# v1.net
KiCad netlist of a schematic drawn in EAGLE
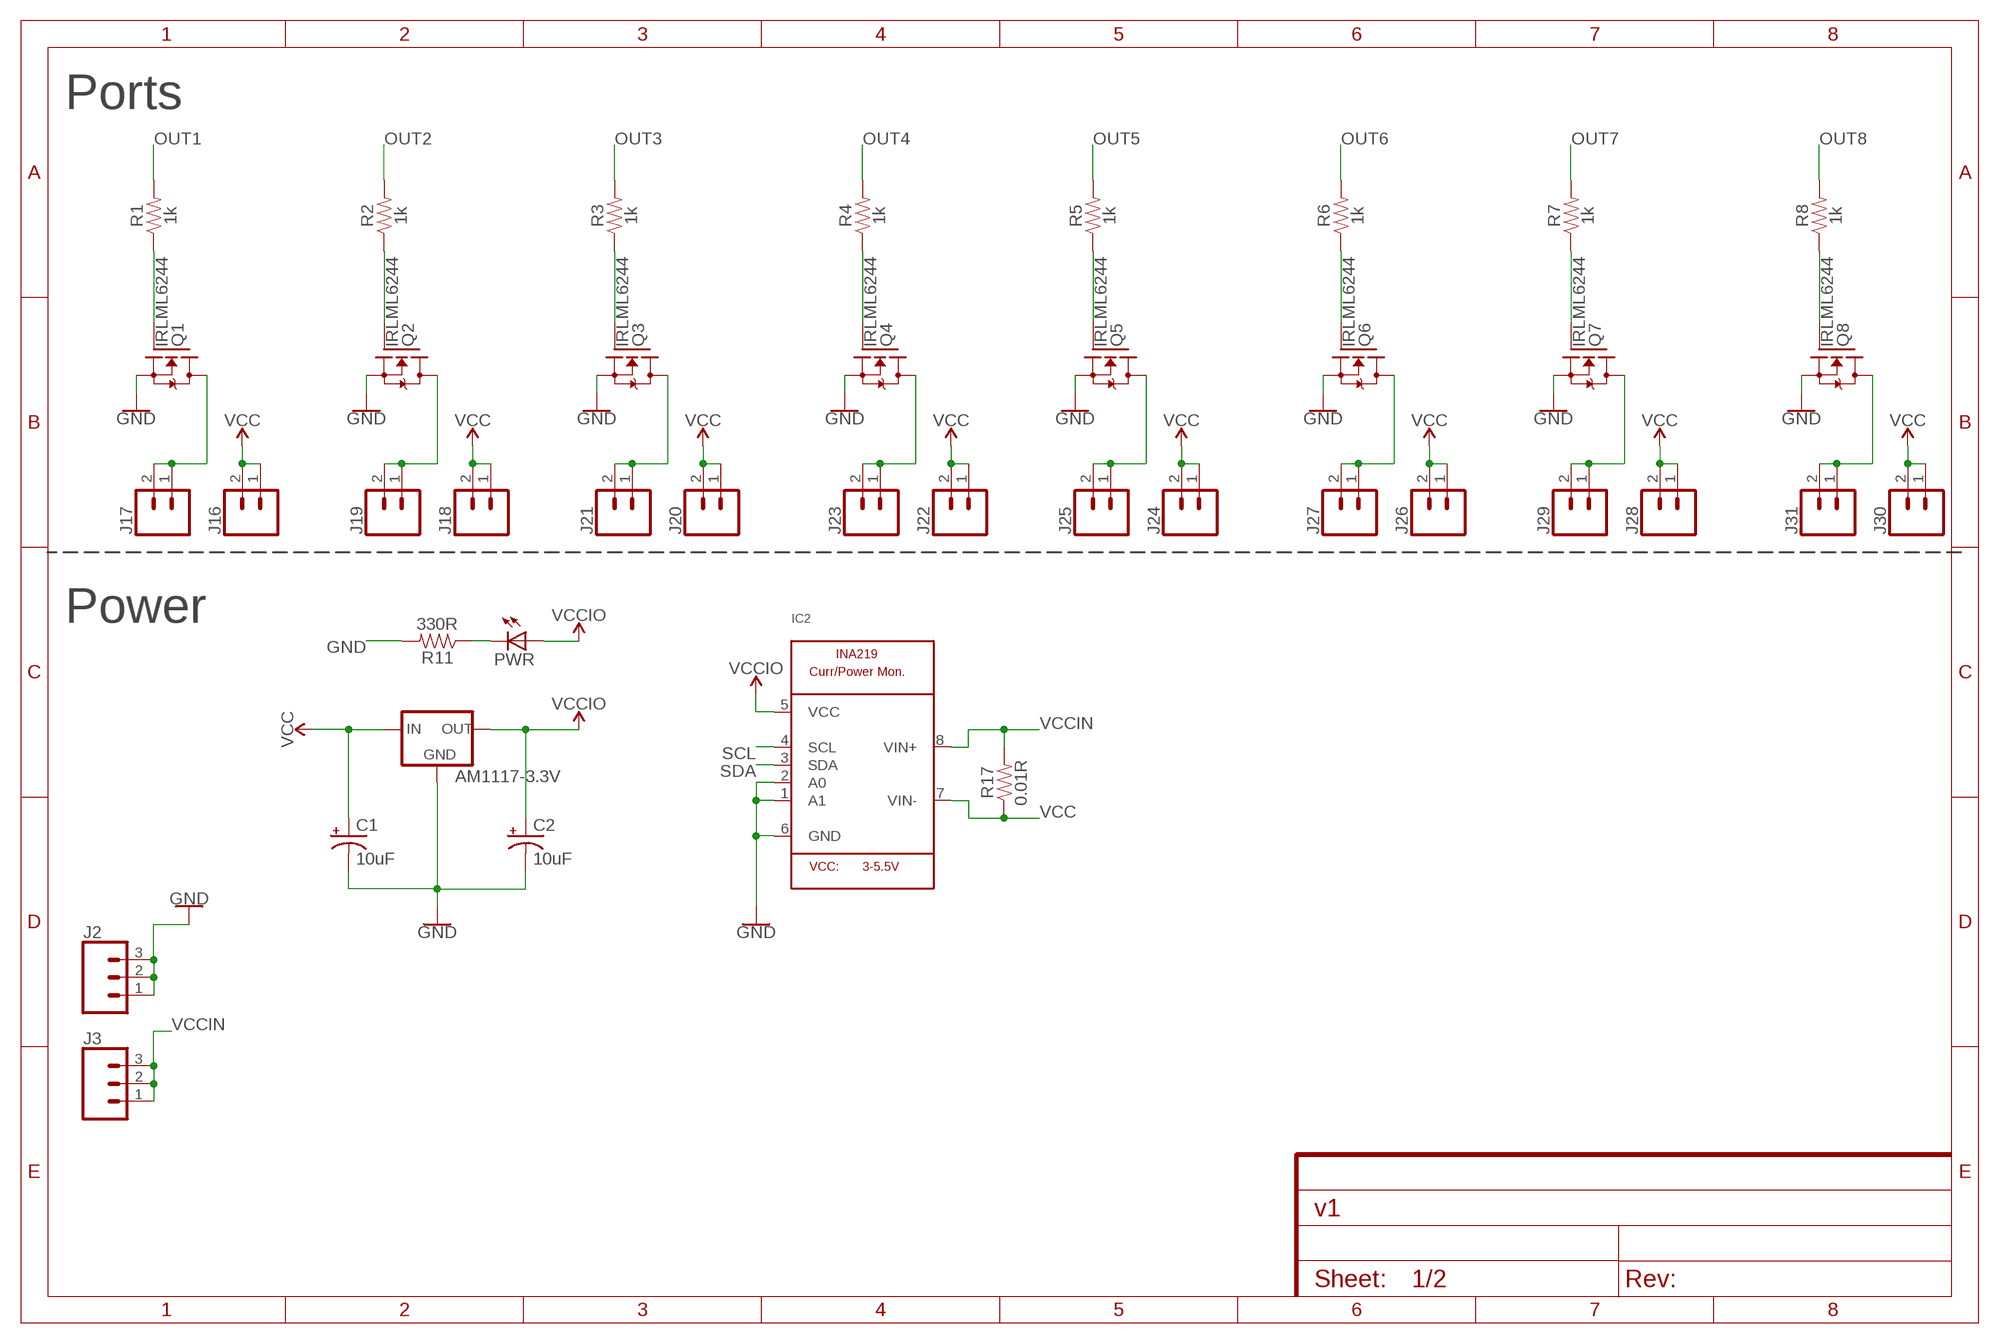
[diagram p0: schematic, sheet 1]
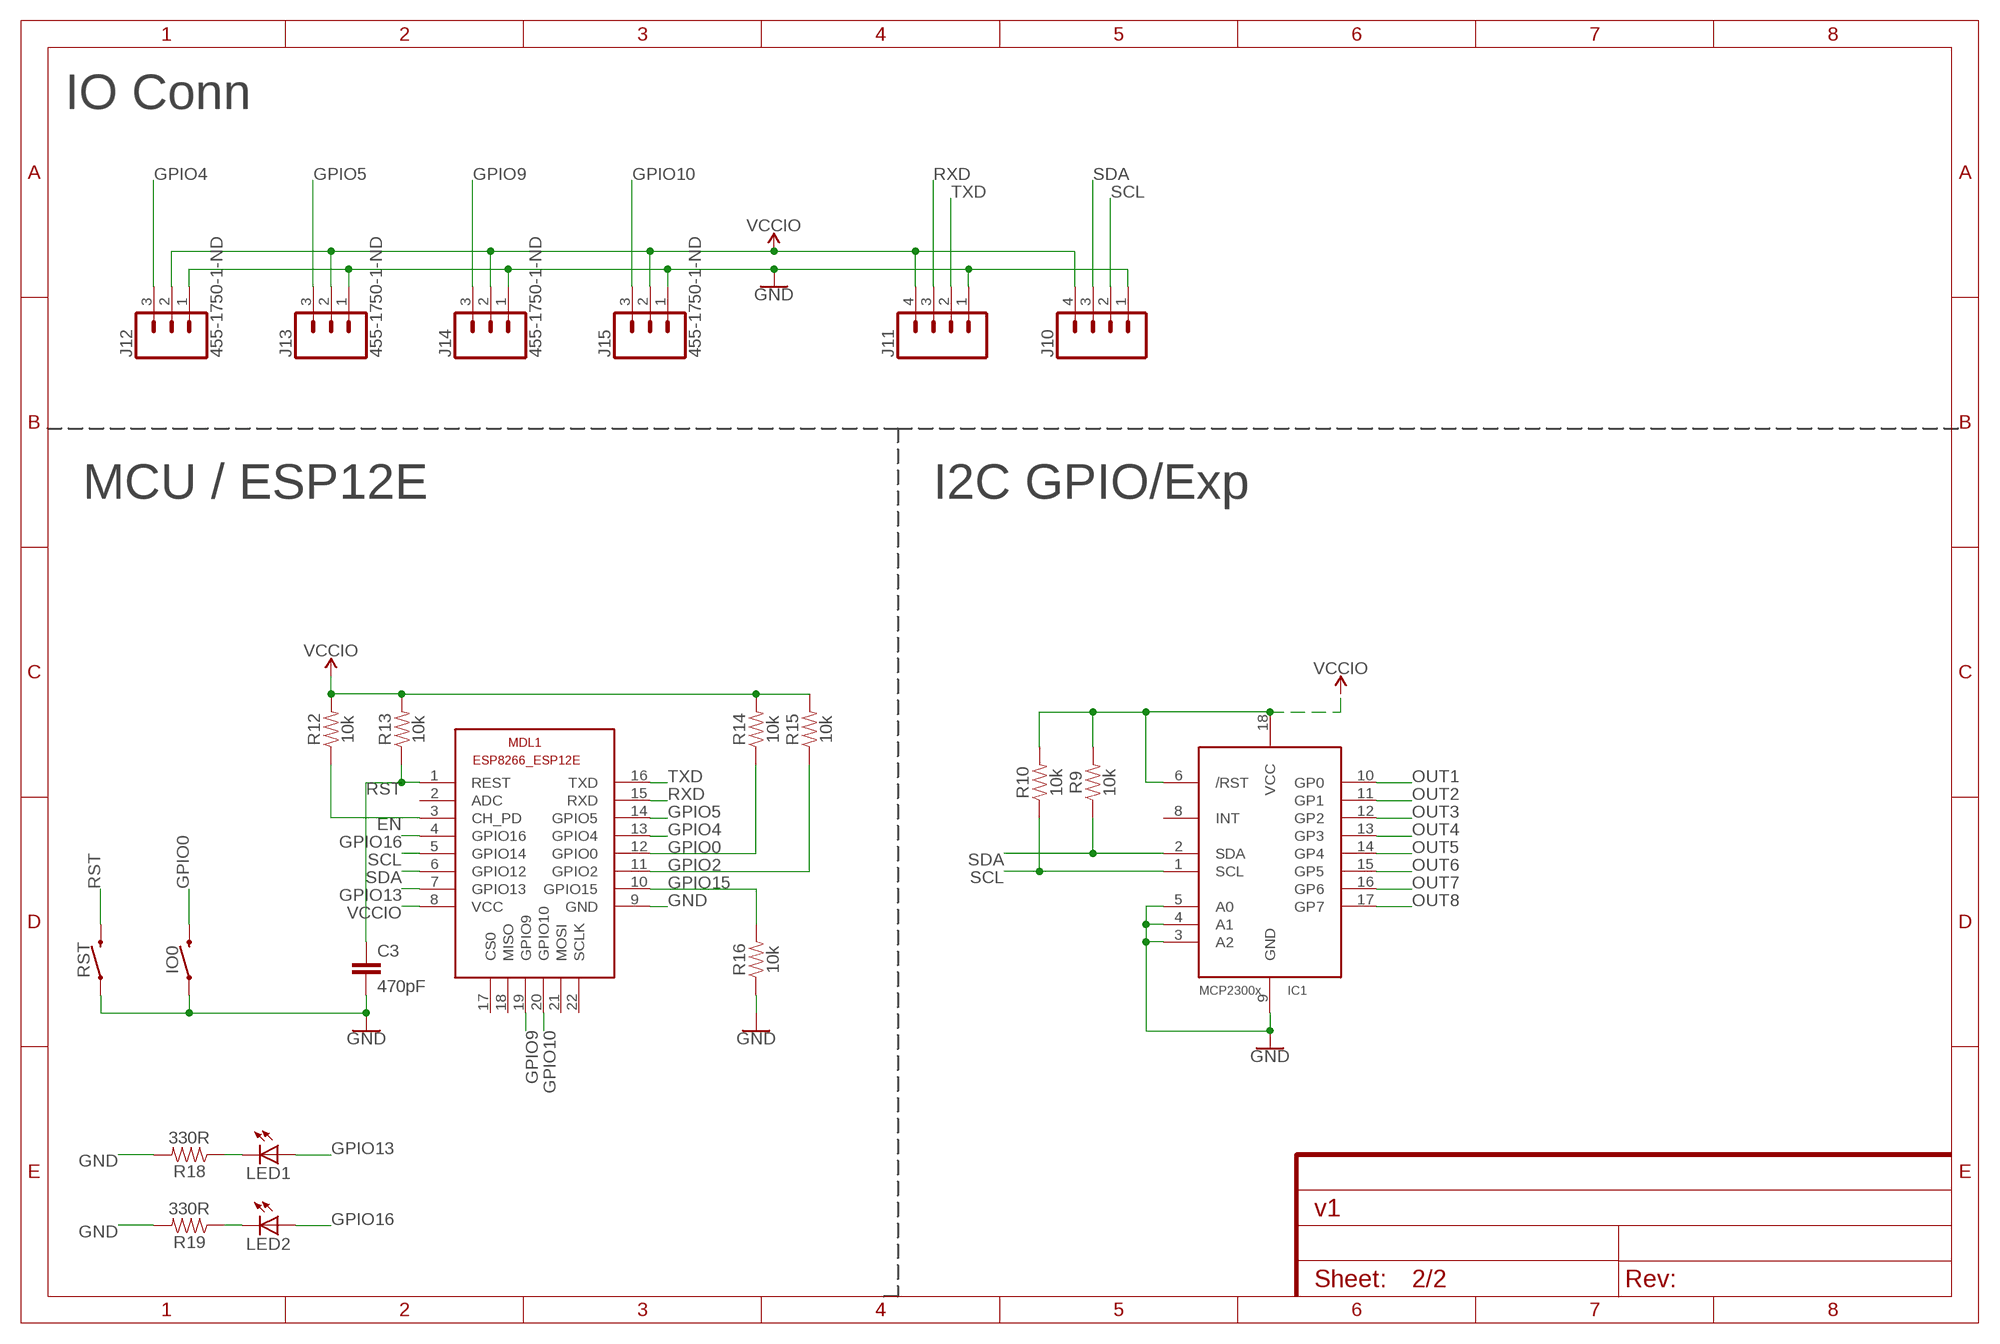
[diagram p1: schematic, sheet 2]

(export (version "E")
  (design (tool "Eeschema 10.0.6"))
  (components
    (comp (ref "AM1117-3.3V")
      (value "V_REG_LD1117VXXLD1117-SMD")
      (footprint "eagle-import:SOT223")
      (libsource (lib "eagle-import") (part "V_REG_LD1117VXXLD1117-SMD"))
    )
    (comp (ref "C1")
      (value "10uF")
      (footprint "eagle-import:EIA3216")
      (libsource (lib "eagle-import") (part "10UF-TANT"))
    )
    (comp (ref "C2")
      (value "10uF")
      (footprint "eagle-import:EIA3216")
      (libsource (lib "eagle-import") (part "10UF-TANT"))
    )
    (comp (ref "IC2")
      (value "INA219SOIC8")
      (footprint "eagle-import:SO08")
      (libsource (lib "eagle-import") (part "INA219SOIC8"))
    )
    (comp (ref "J2")
      (value "CONN_03LONGPADS")
      (footprint "eagle-import:1X03_LONGPADS")
      (libsource (lib "eagle-import") (part "CONN_03LONGPADS"))
    )
    (comp (ref "J3")
      (value "CONN_03LONGPADS")
      (footprint "eagle-import:1X03_LONGPADS")
      (libsource (lib "eagle-import") (part "CONN_03LONGPADS"))
    )
    (comp (ref "J16")
      (value "CONN_02")
      (footprint "eagle-import:1X02")
      (libsource (lib "eagle-import") (part "CONN_02"))
    )
    (comp (ref "J17")
      (value "CONN_02")
      (footprint "eagle-import:1X02")
      (libsource (lib "eagle-import") (part "CONN_02"))
    )
    (comp (ref "J18")
      (value "CONN_02")
      (footprint "eagle-import:1X02")
      (libsource (lib "eagle-import") (part "CONN_02"))
    )
    (comp (ref "J19")
      (value "CONN_02")
      (footprint "eagle-import:1X02")
      (libsource (lib "eagle-import") (part "CONN_02"))
    )
    (comp (ref "J20")
      (value "CONN_02")
      (footprint "eagle-import:1X02")
      (libsource (lib "eagle-import") (part "CONN_02"))
    )
    (comp (ref "J21")
      (value "CONN_02")
      (footprint "eagle-import:1X02")
      (libsource (lib "eagle-import") (part "CONN_02"))
    )
    (comp (ref "J22")
      (value "CONN_02")
      (footprint "eagle-import:1X02")
      (libsource (lib "eagle-import") (part "CONN_02"))
    )
    (comp (ref "J23")
      (value "CONN_02")
      (footprint "eagle-import:1X02")
      (libsource (lib "eagle-import") (part "CONN_02"))
    )
    (comp (ref "J24")
      (value "CONN_02")
      (footprint "eagle-import:1X02")
      (libsource (lib "eagle-import") (part "CONN_02"))
    )
    (comp (ref "J25")
      (value "CONN_02")
      (footprint "eagle-import:1X02")
      (libsource (lib "eagle-import") (part "CONN_02"))
    )
    (comp (ref "J26")
      (value "CONN_02")
      (footprint "eagle-import:1X02")
      (libsource (lib "eagle-import") (part "CONN_02"))
    )
    (comp (ref "J27")
      (value "CONN_02")
      (footprint "eagle-import:1X02")
      (libsource (lib "eagle-import") (part "CONN_02"))
    )
    (comp (ref "J28")
      (value "CONN_02")
      (footprint "eagle-import:1X02")
      (libsource (lib "eagle-import") (part "CONN_02"))
    )
    (comp (ref "J29")
      (value "CONN_02")
      (footprint "eagle-import:1X02")
      (libsource (lib "eagle-import") (part "CONN_02"))
    )
    (comp (ref "J30")
      (value "CONN_02")
      (footprint "eagle-import:1X02")
      (libsource (lib "eagle-import") (part "CONN_02"))
    )
    (comp (ref "J31")
      (value "CONN_02")
      (footprint "eagle-import:1X02")
      (libsource (lib "eagle-import") (part "CONN_02"))
    )
    (comp (ref "PWR")
      (value "LEDCHIP-LED0805")
      (footprint "eagle-import:CHIP-LED0805")
      (libsource (lib "eagle-import") (part "LEDCHIP-LED0805"))
    )
    (comp (ref "Q1")
      (value "IRLML6244")
      (footprint "eagle-import:SOT23")
      (fields
        (field (name "MF") "Internat. Rectifier")
        (field (name "MPN") "IRLML6244TRPbF")
        (field (name "SPICEPREFIX") "Q")
      )
      (libsource (lib "eagle-import") (part "IRLML6244"))
    )
    (comp (ref "Q2")
      (value "IRLML6244")
      (footprint "eagle-import:SOT23")
      (fields (field (name "MF") "Internat. Rectifier") (field (name "MPN") "IRLML6244TRPbF"))
      (libsource (lib "eagle-import") (part "IRLML6244"))
    )
    (comp (ref "Q3")
      (value "IRLML6244")
      (footprint "eagle-import:SOT23")
      (fields (field (name "MF") "Internat. Rectifier") (field (name "MPN") "IRLML6244TRPbF"))
      (libsource (lib "eagle-import") (part "IRLML6244"))
    )
    (comp (ref "Q4")
      (value "IRLML6244")
      (footprint "eagle-import:SOT23")
      (fields (field (name "MF") "Internat. Rectifier") (field (name "MPN") "IRLML6244TRPbF"))
      (libsource (lib "eagle-import") (part "IRLML6244"))
    )
    (comp (ref "Q5")
      (value "IRLML6244")
      (footprint "eagle-import:SOT23")
      (fields (field (name "MF") "Internat. Rectifier") (field (name "MPN") "IRLML6244TRPbF"))
      (libsource (lib "eagle-import") (part "IRLML6244"))
    )
    (comp (ref "Q6")
      (value "IRLML6244")
      (footprint "eagle-import:SOT23")
      (fields (field (name "MF") "Internat. Rectifier") (field (name "MPN") "IRLML6244TRPbF"))
      (libsource (lib "eagle-import") (part "IRLML6244"))
    )
    (comp (ref "Q7")
      (value "IRLML6244")
      (footprint "eagle-import:SOT23")
      (fields (field (name "MF") "Internat. Rectifier") (field (name "MPN") "IRLML6244TRPbF"))
      (libsource (lib "eagle-import") (part "IRLML6244"))
    )
    (comp (ref "Q8")
      (value "IRLML6244")
      (footprint "eagle-import:SOT23")
      (fields (field (name "MF") "Internat. Rectifier") (field (name "MPN") "IRLML6244TRPbF"))
      (libsource (lib "eagle-import") (part "IRLML6244"))
    )
    (comp (ref "R1")
      (value "1k")
      (footprint "eagle-import:0805")
      (fields (field (name "SPICEPREFIX") "R"))
      (libsource (lib "eagle-import") (part "RESISTOR0805"))
    )
    (comp (ref "R2")
      (value "1k")
      (footprint "eagle-import:0805")
      (libsource (lib "eagle-import") (part "RESISTOR0805"))
    )
    (comp (ref "R3")
      (value "1k")
      (footprint "eagle-import:0805")
      (libsource (lib "eagle-import") (part "RESISTOR0805"))
    )
    (comp (ref "R4")
      (value "1k")
      (footprint "eagle-import:0805")
      (libsource (lib "eagle-import") (part "RESISTOR0805"))
    )
    (comp (ref "R5")
      (value "1k")
      (footprint "eagle-import:0805")
      (libsource (lib "eagle-import") (part "RESISTOR0805"))
    )
    (comp (ref "R6")
      (value "1k")
      (footprint "eagle-import:0805")
      (libsource (lib "eagle-import") (part "RESISTOR0805"))
    )
    (comp (ref "R7")
      (value "1k")
      (footprint "eagle-import:0805")
      (libsource (lib "eagle-import") (part "RESISTOR0805"))
    )
    (comp (ref "R8")
      (value "1k")
      (footprint "eagle-import:0805")
      (libsource (lib "eagle-import") (part "RESISTOR0805"))
    )
    (comp (ref "R11")
      (value "330R")
      (footprint "eagle-import:0805")
      (libsource (lib "eagle-import") (part "RESISTOR0805"))
    )
    (comp (ref "R17")
      (value "0.01R")
      (footprint "eagle-import:2512")
      (libsource (lib "eagle-import") (part "0.05OHM-2512-3W-1%"))
    )
    (comp (ref "C3")
      (value "470pF")
      (footprint "eagle-import:0805")
      (libsource (lib "eagle-import") (part "1.0UF-0805-25V-(+80/-20%)"))
    )
    (comp (ref "IC1")
      (value "MCP23008/SO")
      (footprint "eagle-import:SO18W")
      (libsource (lib "eagle-import") (part "MCP23008/SO"))
    )
    (comp (ref "IO0")
      (value "MOMENTARY-SWITCH-SPST-SMD-6.0X3.5MM")
      (footprint "eagle-import:TACTILE_SWITCH_SMD_6.0X3.5MM")
      (libsource (lib "eagle-import") (part "MOMENTARY-SWITCH-SPST-SMD-6.0X3.5MM"))
    )
    (comp (ref "J10")
      (value "CONN_04PTH")
      (footprint "eagle-import:1X04")
      (libsource (lib "eagle-import") (part "CONN_04PTH"))
    )
    (comp (ref "J11")
      (value "CONN_04PTH")
      (footprint "eagle-import:1X04")
      (libsource (lib "eagle-import") (part "CONN_04PTH"))
    )
    (comp (ref "J12")
      (value "455-1750-1-ND")
      (footprint "eagle-import:1X03")
      (libsource (lib "eagle-import") (part "CONN_03"))
    )
    (comp (ref "J13")
      (value "455-1750-1-ND")
      (footprint "eagle-import:1X03")
      (libsource (lib "eagle-import") (part "CONN_03"))
    )
    (comp (ref "J14")
      (value "455-1750-1-ND")
      (footprint "eagle-import:1X03")
      (libsource (lib "eagle-import") (part "CONN_03"))
    )
    (comp (ref "J15")
      (value "455-1750-1-ND")
      (footprint "eagle-import:1X03")
      (libsource (lib "eagle-import") (part "CONN_03"))
    )
    (comp (ref "LED1")
      (value "LEDCHIP-LED0805")
      (footprint "eagle-import:CHIP-LED0805")
      (libsource (lib "eagle-import") (part "LEDCHIP-LED0805"))
    )
    (comp (ref "LED2")
      (value "LEDCHIP-LED0805")
      (footprint "eagle-import:CHIP-LED0805")
      (libsource (lib "eagle-import") (part "LEDCHIP-LED0805"))
    )
    (comp (ref "MDL1")
      (value "ESP8266-12EESP8266-ESP12E")
      (footprint "eagle-import:ESP8266-ESP12E")
      (libsource (lib "eagle-import") (part "ESP8266-12EESP8266-ESP12E"))
    )
    (comp (ref "R9")
      (value "10k")
      (footprint "eagle-import:0805")
      (libsource (lib "eagle-import") (part "RESISTOR0805"))
    )
    (comp (ref "R10")
      (value "10k")
      (footprint "eagle-import:0805")
      (libsource (lib "eagle-import") (part "RESISTOR0805"))
    )
    (comp (ref "R12")
      (value "10k")
      (footprint "eagle-import:0805")
      (libsource (lib "eagle-import") (part "RESISTOR0805"))
    )
    (comp (ref "R13")
      (value "10k")
      (footprint "eagle-import:0805")
      (libsource (lib "eagle-import") (part "RESISTOR0805"))
    )
    (comp (ref "R14")
      (value "10k")
      (footprint "eagle-import:0805")
      (libsource (lib "eagle-import") (part "RESISTOR0805"))
    )
    (comp (ref "R15")
      (value "10k")
      (footprint "eagle-import:0805")
      (libsource (lib "eagle-import") (part "RESISTOR0805"))
    )
    (comp (ref "R16")
      (value "10k")
      (footprint "eagle-import:0805")
      (libsource (lib "eagle-import") (part "RESISTOR0805"))
    )
    (comp (ref "R18")
      (value "330R")
      (footprint "eagle-import:0805")
      (libsource (lib "eagle-import") (part "RESISTOR0805"))
    )
    (comp (ref "R19")
      (value "330R")
      (footprint "eagle-import:0805")
      (libsource (lib "eagle-import") (part "RESISTOR0805"))
    )
    (comp (ref "RST")
      (value "MOMENTARY-SWITCH-SPST-SMD-6.0X3.5MM")
      (footprint "eagle-import:TACTILE_SWITCH_SMD_6.0X3.5MM")
      (libsource (lib "eagle-import") (part "MOMENTARY-SWITCH-SPST-SMD-6.0X3.5MM"))
    )
  )
  (nets
    (net (code "1") (name "EN") (class "Default")
      (node (ref "MDL1") (pin "3") (pinfunction "CH_PD_3") (pintype "bidirectional"))
      (node (ref "R12") (pin "1") (pinfunction "1_1") (pintype "passive"))
    )
    (net (code "2") (name "GND") (class "Default")
      (node (ref "AM1117-3.3V") (pin "1") (pinfunction "GND_1") (pintype "input"))
      (node (ref "C1") (pin "C") (pinfunction "-_C") (pintype "passive"))
      (node (ref "C2") (pin "C") (pinfunction "-_C") (pintype "passive"))
      (node (ref "C3") (pin "2") (pinfunction "2_2") (pintype "passive"))
      (node (ref "IC1") (pin "3") (pinfunction "A2_3") (pintype "input"))
      (node (ref "IC1") (pin "4") (pinfunction "A1_4") (pintype "input"))
      (node (ref "IC1") (pin "5") (pinfunction "A0_5") (pintype "input"))
      (node (ref "IC1") (pin "9") (pinfunction "GND_9") (pintype "power_in"))
      (node (ref "IC2") (pin "1") (pinfunction "A1_1") (pintype "bidirectional"))
      (node (ref "IC2") (pin "2") (pinfunction "A0_2") (pintype "bidirectional"))
      (node (ref "IC2") (pin "6") (pinfunction "GND_6") (pintype "bidirectional"))
      (node (ref "IO0") (pin "1") (pinfunction "1_1") (pintype "passive"))
      (node (ref "J10") (pin "1") (pinfunction "1_1") (pintype "passive"))
      (node (ref "J11") (pin "1") (pinfunction "1_1") (pintype "passive"))
      (node (ref "J12") (pin "1") (pinfunction "1_1") (pintype "passive"))
      (node (ref "J13") (pin "1") (pinfunction "1_1") (pintype "passive"))
      (node (ref "J14") (pin "1") (pinfunction "1_1") (pintype "passive"))
      (node (ref "J15") (pin "1") (pinfunction "1_1") (pintype "passive"))
      (node (ref "J2") (pin "1") (pinfunction "1_1") (pintype "passive"))
      (node (ref "J2") (pin "2") (pinfunction "2_2") (pintype "passive"))
      (node (ref "J2") (pin "3") (pinfunction "3_3") (pintype "passive"))
      (node (ref "MDL1") (pin "9") (pinfunction "GND_9") (pintype "bidirectional"))
      (node (ref "Q1") (pin "2") (pinfunction "S_2") (pintype "passive"))
      (node (ref "Q2") (pin "2") (pinfunction "S_2") (pintype "passive"))
      (node (ref "Q3") (pin "2") (pinfunction "S_2") (pintype "passive"))
      (node (ref "Q4") (pin "2") (pinfunction "S_2") (pintype "passive"))
      (node (ref "Q5") (pin "2") (pinfunction "S_2") (pintype "passive"))
      (node (ref "Q6") (pin "2") (pinfunction "S_2") (pintype "passive"))
      (node (ref "Q7") (pin "2") (pinfunction "S_2") (pintype "passive"))
      (node (ref "Q8") (pin "2") (pinfunction "S_2") (pintype "passive"))
      (node (ref "R11") (pin "2") (pinfunction "2_2") (pintype "passive"))
      (node (ref "R16") (pin "1") (pinfunction "1_1") (pintype "passive"))
      (node (ref "R18") (pin "2") (pinfunction "2_2") (pintype "passive"))
      (node (ref "R19") (pin "2") (pinfunction "2_2") (pintype "passive"))
      (node (ref "RST") (pin "1") (pinfunction "1_1") (pintype "passive"))
    )
    (net (code "3") (name "GPIO0") (class "Default")
      (node (ref "IO0") (pin "2") (pinfunction "2_2") (pintype "passive"))
      (node (ref "MDL1") (pin "12") (pinfunction "GPIO0_12") (pintype "bidirectional"))
      (node (ref "R14") (pin "1") (pinfunction "1_1") (pintype "passive"))
    )
    (net (code "4") (name "GPIO2") (class "Default")
      (node (ref "MDL1") (pin "11") (pinfunction "GPIO2_11") (pintype "bidirectional"))
      (node (ref "R15") (pin "1") (pinfunction "1_1") (pintype "passive"))
    )
    (net (code "5") (name "GPIO4") (class "Default")
      (node (ref "J12") (pin "3") (pinfunction "3_3") (pintype "passive"))
      (node (ref "MDL1") (pin "13") (pinfunction "GPIO4_13") (pintype "bidirectional"))
    )
    (net (code "6") (name "GPIO5") (class "Default")
      (node (ref "J13") (pin "3") (pinfunction "3_3") (pintype "passive"))
      (node (ref "MDL1") (pin "14") (pinfunction "GPIO5_14") (pintype "bidirectional"))
    )
    (net (code "7") (name "GPIO9") (class "Default")
      (node (ref "J14") (pin "3") (pinfunction "3_3") (pintype "passive"))
      (node (ref "MDL1") (pin "19") (pinfunction "GPIO9_19") (pintype "bidirectional"))
    )
    (net (code "8") (name "GPIO10") (class "Default")
      (node (ref "J15") (pin "3") (pinfunction "3_3") (pintype "passive"))
      (node (ref "MDL1") (pin "20") (pinfunction "GPIO10_20") (pintype "bidirectional"))
    )
    (net (code "9") (name "GPIO13") (class "Default")
      (node (ref "LED1") (pin "A") (pinfunction "A_A") (pintype "passive"))
      (node (ref "MDL1") (pin "7") (pinfunction "GPIO13_7") (pintype "bidirectional"))
    )
    (net (code "10") (name "GPIO15") (class "Default")
      (node (ref "MDL1") (pin "10") (pinfunction "GPIO15_10") (pintype "bidirectional"))
      (node (ref "R16") (pin "2") (pinfunction "2_2") (pintype "passive"))
    )
    (net (code "11") (name "GPIO16") (class "Default")
      (node (ref "LED2") (pin "A") (pinfunction "A_A") (pintype "passive"))
      (node (ref "MDL1") (pin "4") (pinfunction "GPIO16_4") (pintype "bidirectional"))
    )
    (net (code "12") (name "Net-(LED1-PadC)") (class "Default")
      (node (ref "LED1") (pin "C") (pinfunction "C_C") (pintype "passive"))
      (node (ref "R18") (pin "1") (pinfunction "1_1") (pintype "passive"))
    )
    (net (code "13") (name "Net-(LED2-PadC)") (class "Default")
      (node (ref "LED2") (pin "C") (pinfunction "C_C") (pintype "passive"))
      (node (ref "R19") (pin "1") (pinfunction "1_1") (pintype "passive"))
    )
    (net (code "14") (name "Net-(PWR-PadC)") (class "Default")
      (node (ref "PWR") (pin "C") (pinfunction "C_C") (pintype "passive"))
      (node (ref "R11") (pin "1") (pinfunction "1_1") (pintype "passive"))
    )
    (net (code "15") (name "Net-(Q1-D)") (class "Default")
      (node (ref "J17") (pin "1") (pinfunction "1_1") (pintype "passive"))
      (node (ref "J17") (pin "2") (pinfunction "2_2") (pintype "passive"))
      (node (ref "Q1") (pin "3") (pinfunction "D_3") (pintype "passive"))
    )
    (net (code "16") (name "Net-(Q1-G)") (class "Default")
      (node (ref "Q1") (pin "1") (pinfunction "G_1") (pintype "passive"))
      (node (ref "R1") (pin "1") (pinfunction "1_1") (pintype "passive"))
    )
    (net (code "17") (name "Net-(Q2-D)") (class "Default")
      (node (ref "J19") (pin "1") (pinfunction "1_1") (pintype "passive"))
      (node (ref "J19") (pin "2") (pinfunction "2_2") (pintype "passive"))
      (node (ref "Q2") (pin "3") (pinfunction "D_3") (pintype "passive"))
    )
    (net (code "18") (name "Net-(Q2-G)") (class "Default")
      (node (ref "Q2") (pin "1") (pinfunction "G_1") (pintype "passive"))
      (node (ref "R2") (pin "1") (pinfunction "1_1") (pintype "passive"))
    )
    (net (code "19") (name "Net-(Q3-D)") (class "Default")
      (node (ref "J21") (pin "1") (pinfunction "1_1") (pintype "passive"))
      (node (ref "J21") (pin "2") (pinfunction "2_2") (pintype "passive"))
      (node (ref "Q3") (pin "3") (pinfunction "D_3") (pintype "passive"))
    )
    (net (code "20") (name "Net-(Q3-G)") (class "Default")
      (node (ref "Q3") (pin "1") (pinfunction "G_1") (pintype "passive"))
      (node (ref "R3") (pin "1") (pinfunction "1_1") (pintype "passive"))
    )
    (net (code "21") (name "Net-(Q4-D)") (class "Default")
      (node (ref "J23") (pin "1") (pinfunction "1_1") (pintype "passive"))
      (node (ref "J23") (pin "2") (pinfunction "2_2") (pintype "passive"))
      (node (ref "Q4") (pin "3") (pinfunction "D_3") (pintype "passive"))
    )
    (net (code "22") (name "Net-(Q4-G)") (class "Default")
      (node (ref "Q4") (pin "1") (pinfunction "G_1") (pintype "passive"))
      (node (ref "R4") (pin "1") (pinfunction "1_1") (pintype "passive"))
    )
    (net (code "23") (name "Net-(Q5-D)") (class "Default")
      (node (ref "J25") (pin "1") (pinfunction "1_1") (pintype "passive"))
      (node (ref "J25") (pin "2") (pinfunction "2_2") (pintype "passive"))
      (node (ref "Q5") (pin "3") (pinfunction "D_3") (pintype "passive"))
    )
    (net (code "24") (name "Net-(Q5-G)") (class "Default")
      (node (ref "Q5") (pin "1") (pinfunction "G_1") (pintype "passive"))
      (node (ref "R5") (pin "1") (pinfunction "1_1") (pintype "passive"))
    )
    (net (code "25") (name "Net-(Q6-D)") (class "Default")
      (node (ref "J27") (pin "1") (pinfunction "1_1") (pintype "passive"))
      (node (ref "J27") (pin "2") (pinfunction "2_2") (pintype "passive"))
      (node (ref "Q6") (pin "3") (pinfunction "D_3") (pintype "passive"))
    )
    (net (code "26") (name "Net-(Q6-G)") (class "Default")
      (node (ref "Q6") (pin "1") (pinfunction "G_1") (pintype "passive"))
      (node (ref "R6") (pin "1") (pinfunction "1_1") (pintype "passive"))
    )
    (net (code "27") (name "Net-(Q7-D)") (class "Default")
      (node (ref "J29") (pin "1") (pinfunction "1_1") (pintype "passive"))
      (node (ref "J29") (pin "2") (pinfunction "2_2") (pintype "passive"))
      (node (ref "Q7") (pin "3") (pinfunction "D_3") (pintype "passive"))
    )
    (net (code "28") (name "Net-(Q7-G)") (class "Default")
      (node (ref "Q7") (pin "1") (pinfunction "G_1") (pintype "passive"))
      (node (ref "R7") (pin "1") (pinfunction "1_1") (pintype "passive"))
    )
    (net (code "29") (name "Net-(Q8-D)") (class "Default")
      (node (ref "J31") (pin "1") (pinfunction "1_1") (pintype "passive"))
      (node (ref "J31") (pin "2") (pinfunction "2_2") (pintype "passive"))
      (node (ref "Q8") (pin "3") (pinfunction "D_3") (pintype "passive"))
    )
    (net (code "30") (name "Net-(Q8-G)") (class "Default")
      (node (ref "Q8") (pin "1") (pinfunction "G_1") (pintype "passive"))
      (node (ref "R8") (pin "1") (pinfunction "1_1") (pintype "passive"))
    )
    (net (code "31") (name "OUT1") (class "Default")
      (node (ref "IC1") (pin "10") (pinfunction "GP0_10") (pintype "bidirectional"))
      (node (ref "R1") (pin "2") (pinfunction "2_2") (pintype "passive"))
    )
    (net (code "32") (name "OUT2") (class "Default")
      (node (ref "IC1") (pin "11") (pinfunction "GP1_11") (pintype "bidirectional"))
      (node (ref "R2") (pin "2") (pinfunction "2_2") (pintype "passive"))
    )
    (net (code "33") (name "OUT3") (class "Default")
      (node (ref "IC1") (pin "12") (pinfunction "GP2_12") (pintype "bidirectional"))
      (node (ref "R3") (pin "2") (pinfunction "2_2") (pintype "passive"))
    )
    (net (code "34") (name "OUT4") (class "Default")
      (node (ref "IC1") (pin "13") (pinfunction "GP3_13") (pintype "bidirectional"))
      (node (ref "R4") (pin "2") (pinfunction "2_2") (pintype "passive"))
    )
    (net (code "35") (name "OUT5") (class "Default")
      (node (ref "IC1") (pin "14") (pinfunction "GP4_14") (pintype "bidirectional"))
      (node (ref "R5") (pin "2") (pinfunction "2_2") (pintype "passive"))
    )
    (net (code "36") (name "OUT6") (class "Default")
      (node (ref "IC1") (pin "15") (pinfunction "GP5_15") (pintype "bidirectional"))
      (node (ref "R6") (pin "2") (pinfunction "2_2") (pintype "passive"))
    )
    (net (code "37") (name "OUT7") (class "Default")
      (node (ref "IC1") (pin "16") (pinfunction "GP6_16") (pintype "bidirectional"))
      (node (ref "R7") (pin "2") (pinfunction "2_2") (pintype "passive"))
    )
    (net (code "38") (name "OUT8") (class "Default")
      (node (ref "IC1") (pin "17") (pinfunction "GP7_17") (pintype "bidirectional"))
      (node (ref "R8") (pin "2") (pinfunction "2_2") (pintype "passive"))
    )
    (net (code "39") (name "RST") (class "Default")
      (node (ref "C3") (pin "1") (pinfunction "1_1") (pintype "passive"))
      (node (ref "MDL1") (pin "1") (pinfunction "REST_1") (pintype "bidirectional"))
      (node (ref "R13") (pin "1") (pinfunction "1_1") (pintype "passive"))
      (node (ref "RST") (pin "2") (pinfunction "2_2") (pintype "passive"))
    )
    (net (code "40") (name "RXD") (class "Default")
      (node (ref "J11") (pin "3") (pinfunction "3_3") (pintype "passive"))
      (node (ref "MDL1") (pin "15") (pinfunction "RXD_15") (pintype "bidirectional"))
    )
    (net (code "41") (name "SCL") (class "Default")
      (node (ref "IC1") (pin "1") (pinfunction "SCL_1") (pintype "bidirectional"))
      (node (ref "IC2") (pin "4") (pinfunction "SCL_4") (pintype "bidirectional"))
      (node (ref "J10") (pin "2") (pinfunction "2_2") (pintype "passive"))
      (node (ref "MDL1") (pin "5") (pinfunction "GPIO14_5") (pintype "bidirectional"))
      (node (ref "R10") (pin "1") (pinfunction "1_1") (pintype "passive"))
    )
    (net (code "42") (name "SDA") (class "Default")
      (node (ref "IC1") (pin "2") (pinfunction "SDA_2") (pintype "bidirectional"))
      (node (ref "IC2") (pin "3") (pinfunction "SDA_3") (pintype "bidirectional"))
      (node (ref "J10") (pin "3") (pinfunction "3_3") (pintype "passive"))
      (node (ref "MDL1") (pin "6") (pinfunction "GPIO12_6") (pintype "bidirectional"))
      (node (ref "R9") (pin "1") (pinfunction "1_1") (pintype "passive"))
    )
    (net (code "43") (name "TXD") (class "Default")
      (node (ref "J11") (pin "2") (pinfunction "2_2") (pintype "passive"))
      (node (ref "MDL1") (pin "16") (pinfunction "TXD_16") (pintype "bidirectional"))
    )
    (net (code "44") (name "VCC") (class "Default")
      (node (ref "AM1117-3.3V") (pin "3") (pinfunction "IN_3") (pintype "input"))
      (node (ref "C1") (pin "A") (pinfunction "+_A") (pintype "passive"))
      (node (ref "IC2") (pin "7") (pinfunction "VIN-_7") (pintype "bidirectional"))
      (node (ref "J16") (pin "1") (pinfunction "1_1") (pintype "passive"))
      (node (ref "J16") (pin "2") (pinfunction "2_2") (pintype "passive"))
      (node (ref "J18") (pin "1") (pinfunction "1_1") (pintype "passive"))
      (node (ref "J18") (pin "2") (pinfunction "2_2") (pintype "passive"))
      (node (ref "J20") (pin "1") (pinfunction "1_1") (pintype "passive"))
      (node (ref "J20") (pin "2") (pinfunction "2_2") (pintype "passive"))
      (node (ref "J22") (pin "1") (pinfunction "1_1") (pintype "passive"))
      (node (ref "J22") (pin "2") (pinfunction "2_2") (pintype "passive"))
      (node (ref "J24") (pin "1") (pinfunction "1_1") (pintype "passive"))
      (node (ref "J24") (pin "2") (pinfunction "2_2") (pintype "passive"))
      (node (ref "J26") (pin "1") (pinfunction "1_1") (pintype "passive"))
      (node (ref "J26") (pin "2") (pinfunction "2_2") (pintype "passive"))
      (node (ref "J28") (pin "1") (pinfunction "1_1") (pintype "passive"))
      (node (ref "J28") (pin "2") (pinfunction "2_2") (pintype "passive"))
      (node (ref "J30") (pin "1") (pinfunction "1_1") (pintype "passive"))
      (node (ref "J30") (pin "2") (pinfunction "2_2") (pintype "passive"))
      (node (ref "R17") (pin "P$1") (pinfunction "1_P$1") (pintype "passive"))
    )
    (net (code "45") (name "VCCIN") (class "Default")
      (node (ref "IC2") (pin "8") (pinfunction "VIN+_8") (pintype "bidirectional"))
      (node (ref "J3") (pin "1") (pinfunction "1_1") (pintype "passive"))
      (node (ref "J3") (pin "2") (pinfunction "2_2") (pintype "passive"))
      (node (ref "J3") (pin "3") (pinfunction "3_3") (pintype "passive"))
      (node (ref "R17") (pin "P$2") (pinfunction "2_P$2") (pintype "passive"))
    )
    (net (code "46") (name "VCCIO") (class "Default")
      (node (ref "AM1117-3.3V") (pin "2") (pinfunction "OUT_2") (pintype "passive"))
      (node (ref "C2") (pin "A") (pinfunction "+_A") (pintype "passive"))
      (node (ref "IC1") (pin "18") (pinfunction "VCC_18") (pintype "power_in"))
      (node (ref "IC1") (pin "6") (pinfunction "/RST_6") (pintype "input"))
      (node (ref "IC2") (pin "5") (pinfunction "VCC_5") (pintype "bidirectional"))
      (node (ref "J10") (pin "4") (pinfunction "4_4") (pintype "passive"))
      (node (ref "J11") (pin "4") (pinfunction "4_4") (pintype "passive"))
      (node (ref "J12") (pin "2") (pinfunction "2_2") (pintype "passive"))
      (node (ref "J13") (pin "2") (pinfunction "2_2") (pintype "passive"))
      (node (ref "J14") (pin "2") (pinfunction "2_2") (pintype "passive"))
      (node (ref "J15") (pin "2") (pinfunction "2_2") (pintype "passive"))
      (node (ref "MDL1") (pin "8") (pinfunction "VCC_8") (pintype "bidirectional"))
      (node (ref "PWR") (pin "A") (pinfunction "A_A") (pintype "passive"))
      (node (ref "R10") (pin "2") (pinfunction "2_2") (pintype "passive"))
      (node (ref "R12") (pin "2") (pinfunction "2_2") (pintype "passive"))
      (node (ref "R13") (pin "2") (pinfunction "2_2") (pintype "passive"))
      (node (ref "R14") (pin "2") (pinfunction "2_2") (pintype "passive"))
      (node (ref "R15") (pin "2") (pinfunction "2_2") (pintype "passive"))
      (node (ref "R9") (pin "2") (pinfunction "2_2") (pintype "passive"))
    )
    (net (code "47") (name "unconnected-(IC1-INT-Pad8)") (class "Default")
      (node (ref "IC1") (pin "8") (pinfunction "INT_8") (pintype "output"))
    )
    (net (code "48") (name "unconnected-(MDL1-ADC-Pad2)") (class "Default")
      (node (ref "MDL1") (pin "2") (pinfunction "ADC_2") (pintype "bidirectional"))
    )
    (net (code "49") (name "unconnected-(MDL1-CS0-Pad17)") (class "Default")
      (node (ref "MDL1") (pin "17") (pinfunction "CS0_17") (pintype "bidirectional"))
    )
    (net (code "50") (name "unconnected-(MDL1-MISO-Pad18)") (class "Default")
      (node (ref "MDL1") (pin "18") (pinfunction "MISO_18") (pintype "bidirectional"))
    )
    (net (code "51") (name "unconnected-(MDL1-MOSI-Pad21)") (class "Default")
      (node (ref "MDL1") (pin "21") (pinfunction "MOSI_21") (pintype "bidirectional"))
    )
    (net (code "52") (name "unconnected-(MDL1-SCLK-Pad22)") (class "Default")
      (node (ref "MDL1") (pin "22") (pinfunction "SCLK_22") (pintype "bidirectional"))
    )
  )
)
